# node.net
KiCad netlist of a schematic drawn in EAGLE
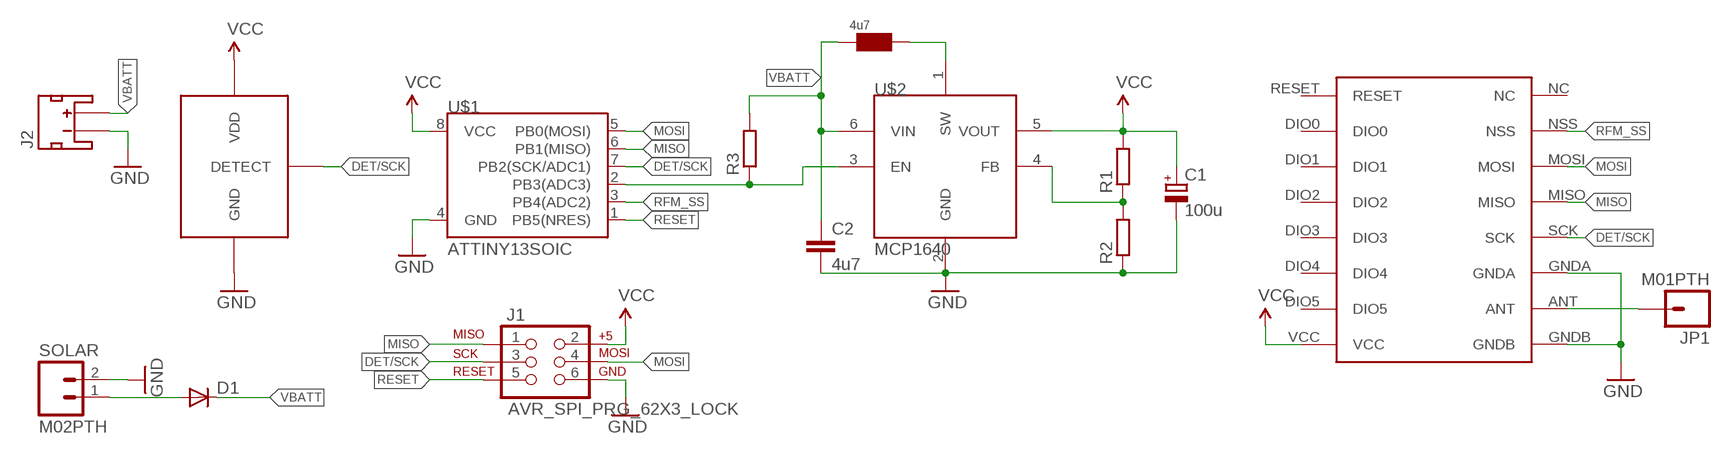
[diagram p0: schematic, sheet 1]

(export (version "E")
  (design (tool "Eeschema 10.0.6"))
  (components
    (comp (ref "C1")
      (value "100u")
      (footprint "eagle-import:SANYO-OSCON_SMD_C6")
      (libsource (lib "eagle-import") (part "CPOL-EUSANYO_SMD_C6"))
    )
    (comp (ref "C2")
      (value "4u7")
      (footprint "eagle-import:C0603")
      (libsource (lib "eagle-import") (part "C-EUC0603"))
    )
    (comp (ref "D1")
      (value "DIODE-SOD123")
      (footprint "eagle-import:SOD123")
      (libsource (lib "eagle-import") (part "DIODE-SOD123"))
    )
    (comp (ref "DF")
      (value "4u7")
      (footprint "eagle-import:BOURNS_SRN5040_L")
      (libsource (lib "eagle-import") (part "BOURNS_SRN5040"))
    )
    (comp (ref "J1")
      (value "AVR_SPI_PRG_62X3_LOCK")
      (footprint "eagle-import:2X3_LOCK")
      (libsource (lib "eagle-import") (part "AVR_SPI_PRG_62X3_LOCK"))
    )
    (comp (ref "J2")
      (value "JST_2MM_MALE_TH")
      (footprint "eagle-import:JST-2-TH")
      (libsource (lib "eagle-import") (part "JST_2MM_MALE_TH"))
    )
    (comp (ref "JP1")
      (value "M01PTH")
      (footprint "eagle-import:1X01")
      (libsource (lib "eagle-import") (part "M01PTH"))
    )
    (comp (ref "R1")
      (value "R-EU_R0603")
      (footprint "eagle-import:R0603")
      (libsource (lib "eagle-import") (part "R-EU_R0603"))
    )
    (comp (ref "R2")
      (value "R-EU_R0603")
      (footprint "eagle-import:R0603")
      (libsource (lib "eagle-import") (part "R-EU_R0603"))
    )
    (comp (ref "R3")
      (value "R-EU_R0603")
      (footprint "eagle-import:R0603")
      (libsource (lib "eagle-import") (part "R-EU_R0603"))
    )
    (comp (ref "SOLAR")
      (value "M02PTH")
      (footprint "eagle-import:1X02")
      (libsource (lib "eagle-import") (part "M02PTH"))
    )
    (comp (ref "U$1")
      (value "ATTINY13SOIC")
      (footprint "eagle-import:SO08")
      (libsource (lib "eagle-import") (part "ATTINY13SOIC"))
    )
    (comp (ref "U$2")
      (value "MCP1640")
      (footprint "eagle-import:SOT23-6")
      (libsource (lib "eagle-import") (part "MCP1640"))
    )
    (comp (ref "U$3")
      (value "BU49X_VDET_SOT235")
      (footprint "eagle-import:SOT23-5L")
      (libsource (lib "eagle-import") (part "BU49X_VDET_SOT235"))
    )
    (comp (ref "U$4")
      (value "RFM69HW")
      (footprint "eagle-import:RFM")
      (libsource (lib "eagle-import") (part "RFM69HW"))
    )
  )
  (nets
    (net (code "1") (name "DET{slash}SCK") (class "Default")
      (node (ref "J1") (pin "3") (pinfunction "3_3") (pintype "passive"))
      (node (ref "U$1") (pin "7") (pinfunction "PB2(SCK/ADC1)_7") (pintype "bidirectional"))
      (node (ref "U$3") (pin "1") (pinfunction "DETECT_1") (pintype "bidirectional"))
      (node (ref "U$4") (pin "SCK") (pinfunction "SCK_SCK") (pintype "bidirectional"))
    )
    (net (code "2") (name "GND") (class "Default")
      (node (ref "C1") (pin "-") (pinfunction "-_-") (pintype "passive"))
      (node (ref "C2") (pin "2") (pinfunction "2_2") (pintype "passive"))
      (node (ref "J1") (pin "6") (pinfunction "6_6") (pintype "passive"))
      (node (ref "J2") (pin "2") (pinfunction "-_2") (pintype "bidirectional"))
      (node (ref "R2") (pin "1") (pinfunction "1_1") (pintype "passive"))
      (node (ref "SOLAR") (pin "2") (pinfunction "2_2") (pintype "passive"))
      (node (ref "U$1") (pin "4") (pinfunction "GND_4") (pintype "bidirectional"))
      (node (ref "U$2") (pin "2") (pinfunction "GND_2") (pintype "power_in"))
      (node (ref "U$3") (pin "3") (pinfunction "GND_3") (pintype "bidirectional"))
      (node (ref "U$4") (pin "GNDA") (pinfunction "GNDA_GNDA") (pintype "bidirectional"))
      (node (ref "U$4") (pin "GNDB") (pinfunction "GNDB_GNDB") (pintype "bidirectional"))
    )
    (net (code "3") (name "MISO") (class "Default")
      (node (ref "J1") (pin "1") (pinfunction "1_1") (pintype "passive"))
      (node (ref "U$1") (pin "6") (pinfunction "PB1(MISO)_6") (pintype "bidirectional"))
      (node (ref "U$4") (pin "MISO") (pinfunction "MISO_MISO") (pintype "bidirectional"))
    )
    (net (code "4") (name "MOSI") (class "Default")
      (node (ref "J1") (pin "4") (pinfunction "4_4") (pintype "passive"))
      (node (ref "U$1") (pin "5") (pinfunction "PB0(MOSI)_5") (pintype "bidirectional"))
      (node (ref "U$4") (pin "MOSI") (pinfunction "MOSI_MOSI") (pintype "bidirectional"))
    )
    (net (code "5") (name "Net-(D1-PadA)") (class "Default")
      (node (ref "D1") (pin "A") (pinfunction "A_A") (pintype "passive"))
      (node (ref "SOLAR") (pin "1") (pinfunction "1_1") (pintype "passive"))
    )
    (net (code "6") (name "Net-(JP1-Pad1)") (class "Default")
      (node (ref "JP1") (pin "1") (pinfunction "1_1") (pintype "passive"))
      (node (ref "U$4") (pin "ANT") (pinfunction "ANT_ANT") (pintype "bidirectional"))
    )
    (net (code "7") (name "Net-(U$1-PB3(ADC3))") (class "Default")
      (node (ref "R3") (pin "1") (pinfunction "1_1") (pintype "passive"))
      (node (ref "U$1") (pin "2") (pinfunction "PB3(ADC3)_2") (pintype "bidirectional"))
      (node (ref "U$2") (pin "3") (pinfunction "EN_3") (pintype "input"))
    )
    (net (code "8") (name "Net-(U$2-FB)") (class "Default")
      (node (ref "R1") (pin "1") (pinfunction "1_1") (pintype "passive"))
      (node (ref "R2") (pin "2") (pinfunction "2_2") (pintype "passive"))
      (node (ref "U$2") (pin "4") (pinfunction "FB_4") (pintype "input"))
    )
    (net (code "9") (name "Net-(U$2-SW)") (class "Default")
      (node (ref "DF") (pin "P$2") (pinfunction "P$2_P$2") (pintype "bidirectional"))
      (node (ref "U$2") (pin "1") (pinfunction "SW_1") (pintype "input"))
    )
    (net (code "10") (name "RESET") (class "Default")
      (node (ref "J1") (pin "5") (pinfunction "5_5") (pintype "passive"))
      (node (ref "U$1") (pin "1") (pinfunction "PB5(NRES)_1") (pintype "bidirectional"))
    )
    (net (code "11") (name "RFM_SS") (class "Default")
      (node (ref "U$1") (pin "3") (pinfunction "PB4(ADC2)_3") (pintype "bidirectional"))
      (node (ref "U$4") (pin "NSS") (pinfunction "NSS_NSS") (pintype "bidirectional"))
    )
    (net (code "12") (name "VBATT") (class "Default")
      (node (ref "C2") (pin "1") (pinfunction "1_1") (pintype "passive"))
      (node (ref "D1") (pin "C") (pinfunction "C_C") (pintype "passive"))
      (node (ref "DF") (pin "P$1") (pinfunction "P$1_P$1") (pintype "bidirectional"))
      (node (ref "J2") (pin "1") (pinfunction "+_1") (pintype "bidirectional"))
      (node (ref "R3") (pin "2") (pinfunction "2_2") (pintype "passive"))
      (node (ref "U$2") (pin "6") (pinfunction "VIN_6") (pintype "power_in"))
    )
    (net (code "13") (name "VCC") (class "Default")
      (node (ref "C1") (pin "+") (pinfunction "+_+") (pintype "passive"))
      (node (ref "J1") (pin "2") (pinfunction "2_2") (pintype "passive"))
      (node (ref "R1") (pin "2") (pinfunction "2_2") (pintype "passive"))
      (node (ref "U$1") (pin "8") (pinfunction "VCC_8") (pintype "bidirectional"))
      (node (ref "U$2") (pin "5") (pinfunction "VOUT_5") (pintype "output"))
      (node (ref "U$3") (pin "2") (pinfunction "VDD_2") (pintype "bidirectional"))
      (node (ref "U$4") (pin "VCC") (pinfunction "VCC_VCC") (pintype "bidirectional"))
    )
    (net (code "14") (name "unconnected-(U$4-PadDIO0)") (class "Default")
      (node (ref "U$4") (pin "DIO0") (pinfunction "DIO0_DIO0") (pintype "bidirectional"))
    )
    (net (code "15") (name "unconnected-(U$4-PadDIO1)") (class "Default")
      (node (ref "U$4") (pin "DIO1") (pinfunction "DIO1_DIO1") (pintype "bidirectional"))
    )
    (net (code "16") (name "unconnected-(U$4-PadDIO2)") (class "Default")
      (node (ref "U$4") (pin "DIO2") (pinfunction "DIO2_DIO2") (pintype "bidirectional"))
    )
    (net (code "17") (name "unconnected-(U$4-PadDIO3)") (class "Default")
      (node (ref "U$4") (pin "DIO3") (pinfunction "DIO3_DIO3") (pintype "bidirectional"))
    )
    (net (code "18") (name "unconnected-(U$4-PadDIO4)") (class "Default")
      (node (ref "U$4") (pin "DIO4") (pinfunction "DIO4_DIO4") (pintype "bidirectional"))
    )
    (net (code "19") (name "unconnected-(U$4-PadDIO5)") (class "Default")
      (node (ref "U$4") (pin "DIO5") (pinfunction "DIO5_DIO5") (pintype "bidirectional"))
    )
    (net (code "20") (name "unconnected-(U$4-PadNC)") (class "Default")
      (node (ref "U$4") (pin "NC") (pinfunction "NC_NC") (pintype "bidirectional"))
    )
    (net (code "21") (name "unconnected-(U$4-PadRESET)") (class "Default")
      (node (ref "U$4") (pin "RESET") (pinfunction "RESET_RESET") (pintype "bidirectional"))
    )
  )
)
